# Mouse.net
KiCad netlist of a schematic drawn in EAGLE
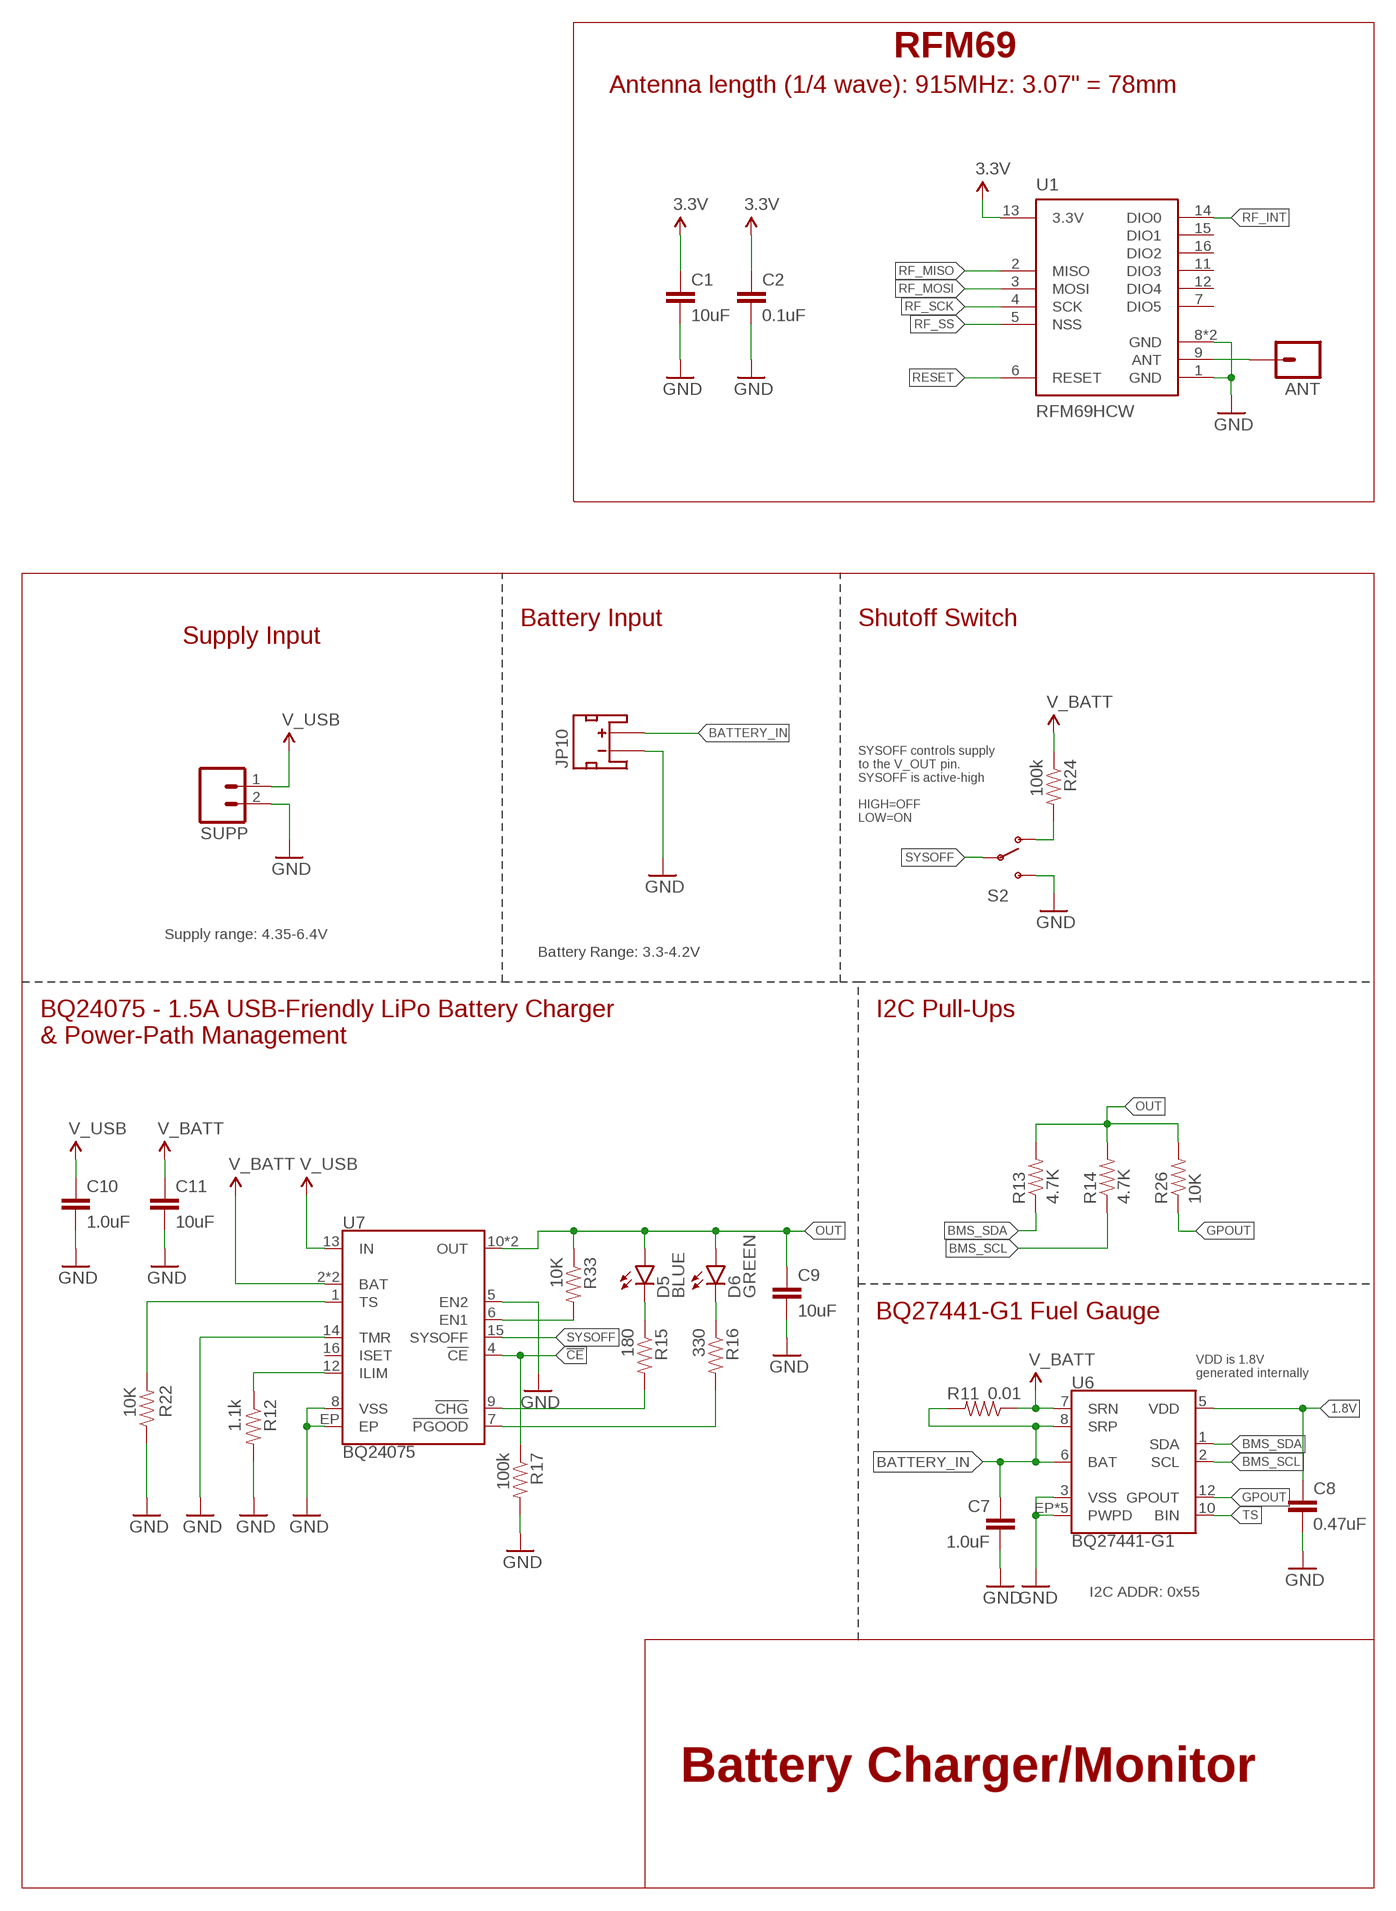
[diagram p0: schematic, sheet 1, part 1 of 2]
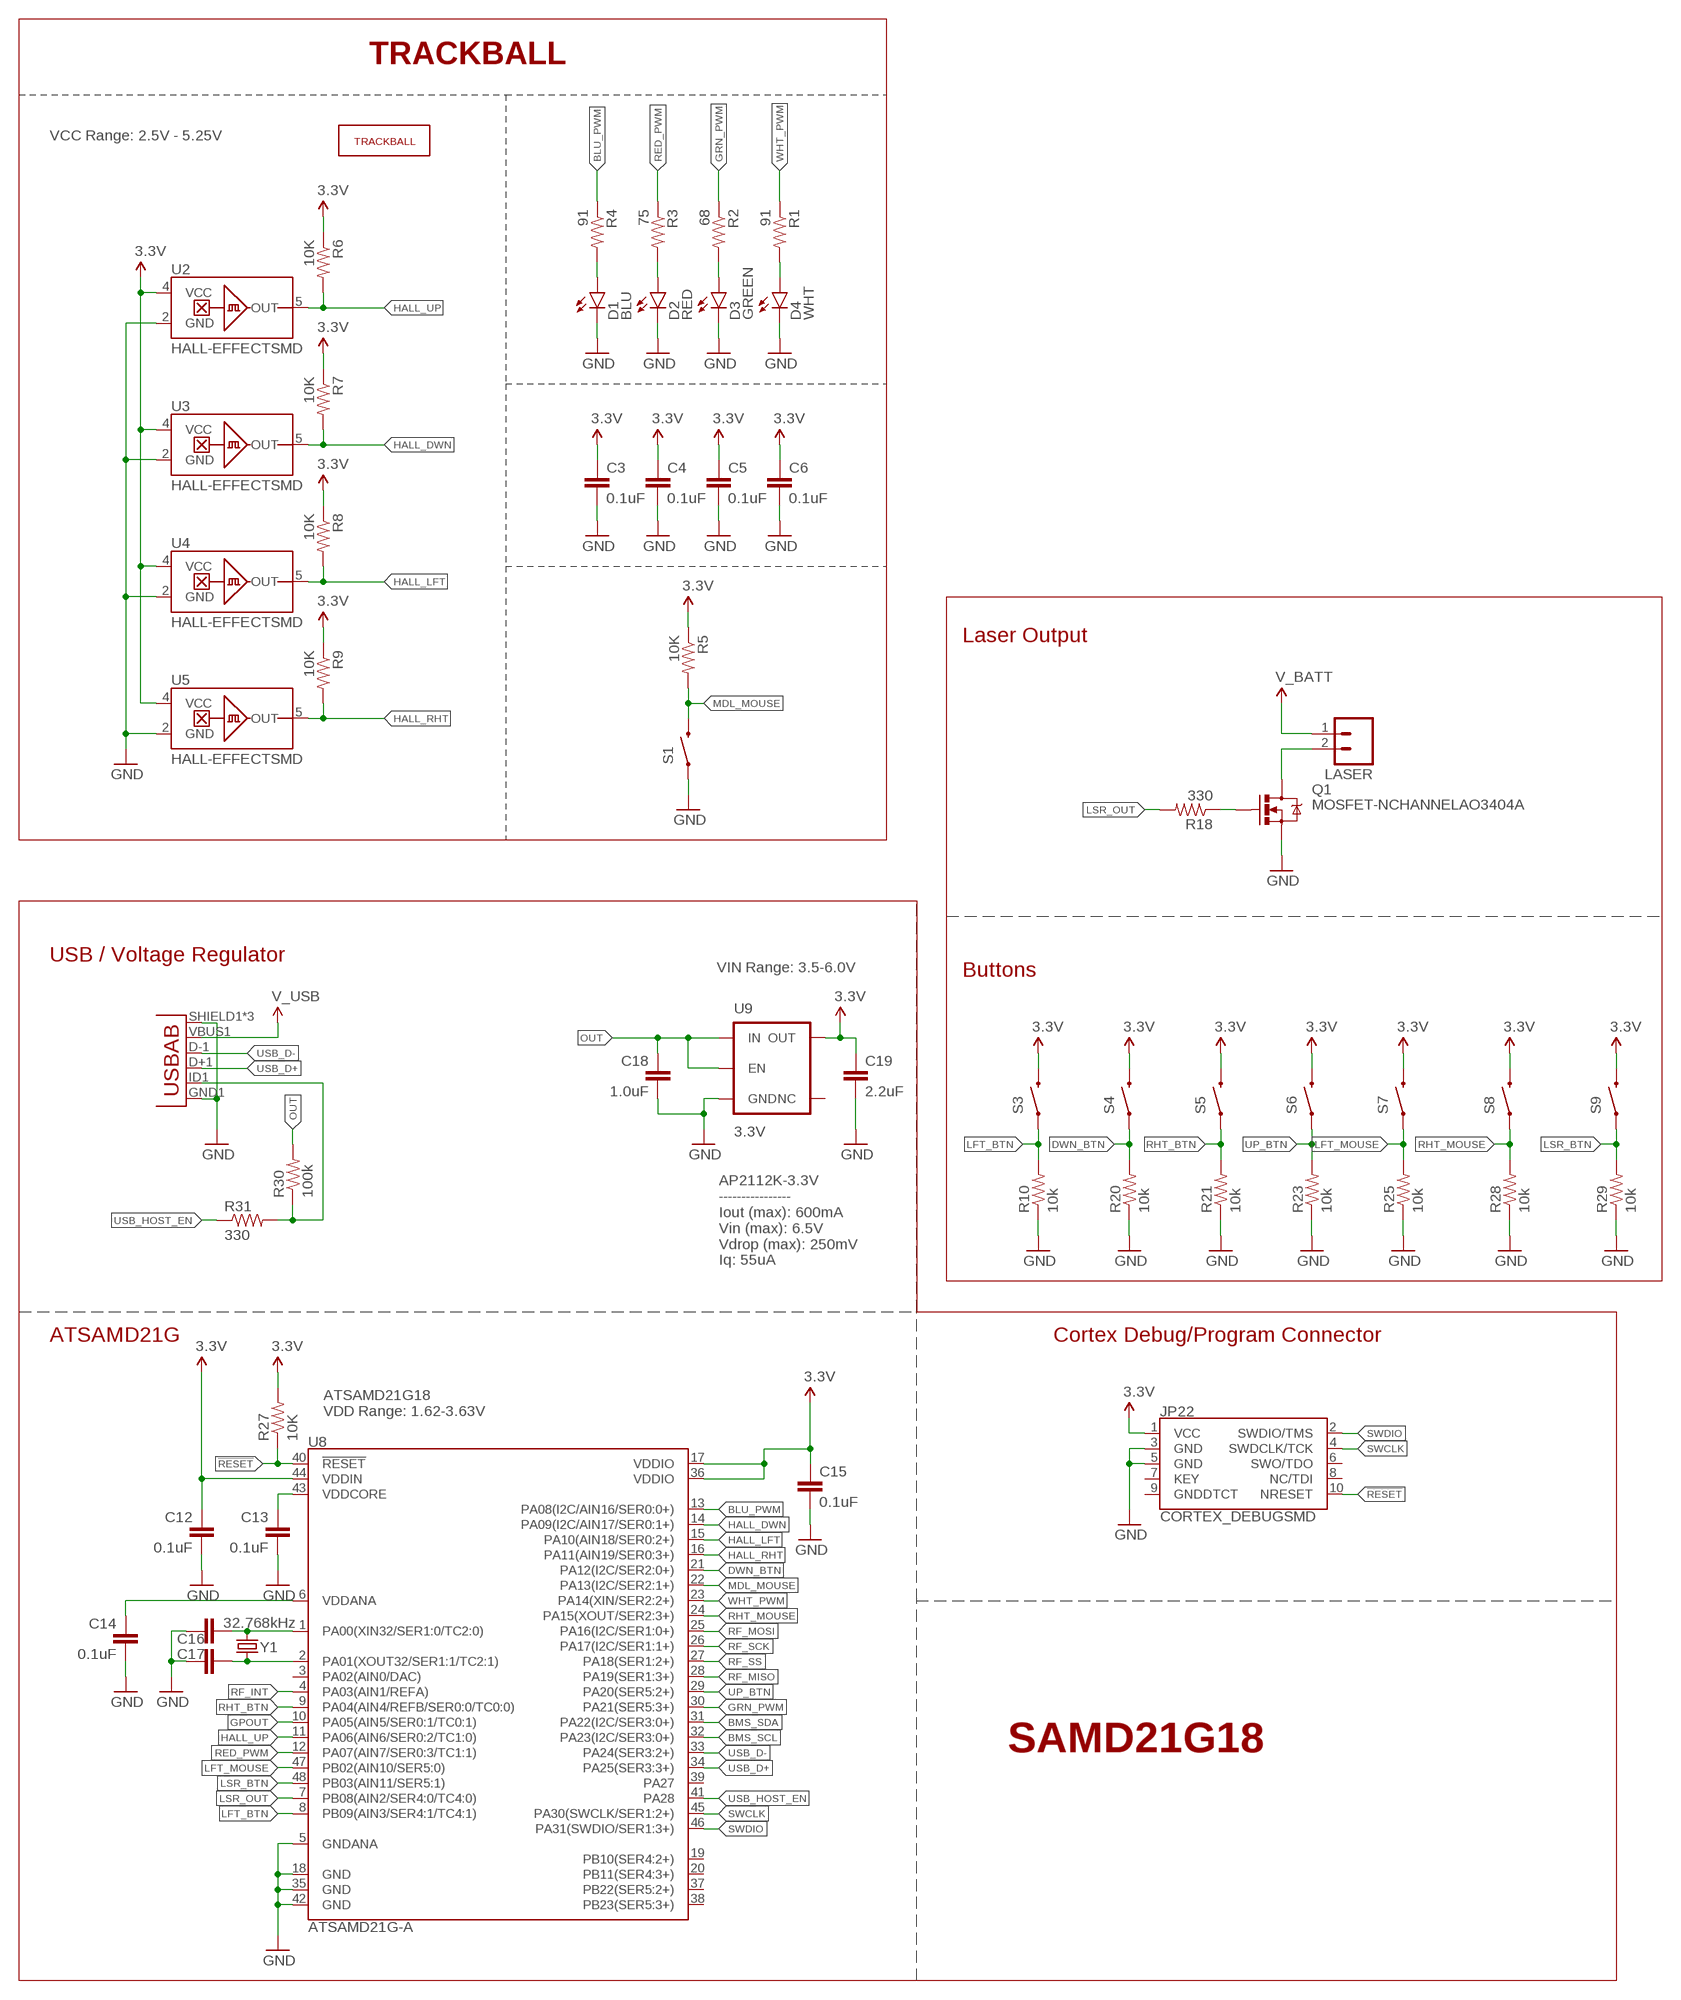
[diagram p1: schematic, sheet 1, part 2 of 2]

(export (version "E")
  (design (tool "Eeschema 10.0.6"))
  (components
    (comp (ref "ANT")
      (value "M01PTH_NO_SILK_YES_STOP")
      (footprint "eagle-import:1X01_NO_SILK")
      (libsource (lib "eagle-import") (part "M01PTH_NO_SILK_YES_STOP"))
    )
    (comp (ref "C1")
      (value "10uF")
      (footprint "eagle-import:1210")
      (libsource (lib "eagle-import") (part "10UF50V20%(1210)"))
    )
    (comp (ref "C2")
      (value "0.1uF")
      (footprint "eagle-import:0603-CAP")
      (libsource (lib "eagle-import") (part "0.1UF-25V(+80/-20%)(0603)"))
    )
    (comp (ref "C3")
      (value "0.1uF")
      (footprint "eagle-import:0603-CAP")
      (libsource (lib "eagle-import") (part "0.1UF-25V(+80/-20%)(0603)"))
    )
    (comp (ref "C4")
      (value "0.1uF")
      (footprint "eagle-import:0603-CAP")
      (libsource (lib "eagle-import") (part "0.1UF-25V(+80/-20%)(0603)"))
    )
    (comp (ref "C5")
      (value "0.1uF")
      (footprint "eagle-import:0603-CAP")
      (libsource (lib "eagle-import") (part "0.1UF-25V(+80/-20%)(0603)"))
    )
    (comp (ref "C6")
      (value "0.1uF")
      (footprint "eagle-import:0603-CAP")
      (libsource (lib "eagle-import") (part "0.1UF-25V(+80/-20%)(0603)"))
    )
    (comp (ref "C7")
      (value "1.0uF")
      (footprint "eagle-import:0603-CAP")
      (libsource (lib "eagle-import") (part "1.0UF-16V-10%(0603)"))
    )
    (comp (ref "C8")
      (value "0.47uF")
      (footprint "eagle-import:0603-CAP")
      (libsource (lib "eagle-import") (part "CAP0603-CAP"))
    )
    (comp (ref "C9")
      (value "10uF")
      (footprint "eagle-import:0805-CAP")
      (libsource (lib "eagle-import") (part "10UF10V10%(0805)"))
    )
    (comp (ref "C10")
      (value "1.0uF")
      (footprint "eagle-import:1206-CAP")
      (libsource (lib "eagle-import") (part "1.0UF50V10%(1206)"))
    )
    (comp (ref "C11")
      (value "10uF")
      (footprint "eagle-import:0805-CAP")
      (libsource (lib "eagle-import") (part "10UF10V10%(0805)"))
    )
    (comp (ref "C12")
      (value "0.1uF")
      (footprint "eagle-import:0603-CAP")
      (libsource (lib "eagle-import") (part "CAP0603-CAP"))
    )
    (comp (ref "C13")
      (value "0.1uF")
      (footprint "eagle-import:0603-CAP")
      (libsource (lib "eagle-import") (part "CAP0603-CAP"))
    )
    (comp (ref "C14")
      (value "0.1uF")
      (footprint "eagle-import:0603-CAP")
      (libsource (lib "eagle-import") (part "CAP0603-CAP"))
    )
    (comp (ref "C15")
      (value "0.1uF")
      (footprint "eagle-import:0603-CAP")
      (libsource (lib "eagle-import") (part "CAP0603-CAP"))
    )
    (comp (ref "C16")
      (value "15pF")
      (footprint "eagle-import:0603-CAP")
      (libsource (lib "eagle-import") (part "CAP0603-CAP"))
    )
    (comp (ref "C17")
      (value "15pF")
      (footprint "eagle-import:0603-CAP")
      (libsource (lib "eagle-import") (part "CAP0603-CAP"))
    )
    (comp (ref "C18")
      (value "1.0uF")
      (footprint "eagle-import:0805-CAP")
      (libsource (lib "eagle-import") (part "1.0UF-25V-+80/-20(0805){dblquote}"))
    )
    (comp (ref "C19")
      (value "2.2uF")
      (footprint "eagle-import:0603-CAP")
      (libsource (lib "eagle-import") (part "2.2UF-10V-20%(0603)"))
    )
    (comp (ref "D1")
      (value "BLU")
      (footprint "eagle-import:LED-0603")
      (libsource (lib "eagle-import") (part "LED-BLUE0603"))
    )
    (comp (ref "D2")
      (value "RED")
      (footprint "eagle-import:LED-0603")
      (libsource (lib "eagle-import") (part "LED-RED0603"))
    )
    (comp (ref "D3")
      (value "GREEN")
      (footprint "eagle-import:LED-0603")
      (libsource (lib "eagle-import") (part "LED-GREEN0603"))
    )
    (comp (ref "D4")
      (value "WHT")
      (footprint "eagle-import:LED-0603")
      (libsource (lib "eagle-import") (part "LED-WHITE0603"))
    )
    (comp (ref "D5")
      (value "BLUE")
      (footprint "eagle-import:LED-0603")
      (libsource (lib "eagle-import") (part "LED-BLUE0603"))
    )
    (comp (ref "D6")
      (value "GREEN")
      (footprint "eagle-import:LED-0603")
      (libsource (lib "eagle-import") (part "LED-RED0603"))
    )
    (comp (ref "JP10")
      (value "JST_2MM_MALE")
      (footprint "eagle-import:JST-2-SMD")
      (libsource (lib "eagle-import") (part "JST_2MM_MALE"))
    )
    (comp (ref "JP22")
      (value "CORTEX_DEBUGSMD")
      (footprint "eagle-import:SAMTECH_FTSH-105-01")
      (libsource (lib "eagle-import") (part "CORTEX_DEBUGSMD"))
    )
    (comp (ref "JP23")
      (value "USB-ABCONN-11794")
      (footprint "eagle-import:USB-AB-MICRO-SMD_V03")
      (libsource (lib "eagle-import") (part "USB-ABCONN-11794"))
    )
    (comp (ref "LASER")
      (value "M021X02_NO_SILK")
      (footprint "eagle-import:1X02_NO_SILK")
      (libsource (lib "eagle-import") (part "M021X02_NO_SILK"))
    )
    (comp (ref "Q1")
      (value "MOSFET-NCHANNELAO3404A")
      (footprint "eagle-import:SOT23-3")
      (libsource (lib "eagle-import") (part "MOSFET-NCHANNELAO3404A"))
    )
    (comp (ref "R1")
      (value "91")
      (footprint "eagle-import:0603-RES@2")
      (libsource (lib "eagle-import") (part "180OHM1/10W1%(0603)"))
    )
    (comp (ref "R2")
      (value "68")
      (footprint "eagle-import:0603-RES@2")
      (libsource (lib "eagle-import") (part "180OHM1/10W1%(0603)"))
    )
    (comp (ref "R3")
      (value "75")
      (footprint "eagle-import:0603-RES@2")
      (libsource (lib "eagle-import") (part "180OHM1/10W1%(0603)"))
    )
    (comp (ref "R4")
      (value "91")
      (footprint "eagle-import:0603-RES@2")
      (libsource (lib "eagle-import") (part "180OHM1/10W1%(0603)"))
    )
    (comp (ref "R5")
      (value "10K")
      (footprint "eagle-import:0603-RES@1")
      (libsource (lib "eagle-import") (part "10KOHM1/10W1%(0603)0603"))
    )
    (comp (ref "R6")
      (value "10K")
      (footprint "eagle-import:0603-RES@1")
      (libsource (lib "eagle-import") (part "10KOHM1/10W1%(0603)0603"))
    )
    (comp (ref "R7")
      (value "10K")
      (footprint "eagle-import:0603-RES@1")
      (libsource (lib "eagle-import") (part "10KOHM1/10W1%(0603)0603"))
    )
    (comp (ref "R8")
      (value "10K")
      (footprint "eagle-import:0603-RES@1")
      (libsource (lib "eagle-import") (part "10KOHM1/10W1%(0603)0603"))
    )
    (comp (ref "R9")
      (value "10K")
      (footprint "eagle-import:0603-RES@1")
      (libsource (lib "eagle-import") (part "10KOHM1/10W1%(0603)0603"))
    )
    (comp (ref "R10")
      (value "10k")
      (footprint "eagle-import:0603-RES")
      (libsource (lib "eagle-import") (part "330OHM1/10W1%(0603)"))
    )
    (comp (ref "R11")
      (value "0.01")
      (footprint "eagle-import:1206")
      (libsource (lib "eagle-import") (part "SparkFun-Resistors_RESISTOR1206"))
    )
    (comp (ref "R12")
      (value "1.1k")
      (footprint "eagle-import:0603-RES")
      (libsource (lib "eagle-import") (part "RESISTOR0603-RES"))
    )
    (comp (ref "R13")
      (value "4.7K")
      (footprint "eagle-import:0603-RES@2")
      (libsource (lib "eagle-import") (part "4.7KOHM-1/10W-1%(0603)"))
    )
    (comp (ref "R14")
      (value "4.7K")
      (footprint "eagle-import:0603-RES@2")
      (libsource (lib "eagle-import") (part "4.7KOHM-1/10W-1%(0603)"))
    )
    (comp (ref "R15")
      (value "180")
      (footprint "eagle-import:0603-RES@2")
      (libsource (lib "eagle-import") (part "180OHM1/10W1%(0603)"))
    )
    (comp (ref "R16")
      (value "330")
      (footprint "eagle-import:0603-RES@2")
      (libsource (lib "eagle-import") (part "1KOHM-1/10W-1%(0603)"))
    )
    (comp (ref "R17")
      (value "100k")
      (footprint "eagle-import:0603-RES")
      (libsource (lib "eagle-import") (part "100KOHM-1/10W-1%(0603)"))
    )
    (comp (ref "R18")
      (value "330")
      (footprint "eagle-import:0603-RES")
      (libsource (lib "eagle-import") (part "330OHM1/10W1%(0603)"))
    )
    (comp (ref "R20")
      (value "10k")
      (footprint "eagle-import:0603-RES")
      (libsource (lib "eagle-import") (part "330OHM1/10W1%(0603)"))
    )
    (comp (ref "R21")
      (value "10k")
      (footprint "eagle-import:0603-RES")
      (libsource (lib "eagle-import") (part "330OHM1/10W1%(0603)"))
    )
    (comp (ref "R22")
      (value "10K")
      (footprint "eagle-import:0603-RES")
      (libsource (lib "eagle-import") (part "10KOHM-1/10W-1%(0603)0603"))
    )
    (comp (ref "R23")
      (value "10k")
      (footprint "eagle-import:0603-RES")
      (libsource (lib "eagle-import") (part "330OHM1/10W1%(0603)"))
    )
    (comp (ref "R24")
      (value "100k")
      (footprint "eagle-import:0603-RES")
      (libsource (lib "eagle-import") (part "100KOHM-1/10W-1%(0603)"))
    )
    (comp (ref "R25")
      (value "10k")
      (footprint "eagle-import:0603-RES")
      (libsource (lib "eagle-import") (part "330OHM1/10W1%(0603)"))
    )
    (comp (ref "R26")
      (value "10K")
      (footprint "eagle-import:0603-RES")
      (libsource (lib "eagle-import") (part "10KOHM-1/10W-1%(0603)0603"))
    )
    (comp (ref "R27")
      (value "10K")
      (footprint "eagle-import:0603-RES")
      (libsource (lib "eagle-import") (part "10KOHM-1/10W-1%(0603)0603"))
    )
    (comp (ref "R28")
      (value "10k")
      (footprint "eagle-import:0603-RES")
      (libsource (lib "eagle-import") (part "330OHM1/10W1%(0603)"))
    )
    (comp (ref "R29")
      (value "10k")
      (footprint "eagle-import:0603-RES")
      (libsource (lib "eagle-import") (part "330OHM1/10W1%(0603)"))
    )
    (comp (ref "R30")
      (value "100k")
      (footprint "eagle-import:0603-RES")
      (libsource (lib "eagle-import") (part "100KOHM-1/10W-1%(0603)"))
    )
    (comp (ref "R31")
      (value "330")
      (footprint "eagle-import:0603-RES")
      (libsource (lib "eagle-import") (part "330OHM1/10W1%(0603)"))
    )
    (comp (ref "R33")
      (value "10K")
      (footprint "eagle-import:0603-RES")
      (libsource (lib "eagle-import") (part "10KOHM-1/10W-1%(0603)0603"))
    )
    (comp (ref "S1")
      (value "SWITCH-MOMENTARY-2SMD-2")
      (footprint "eagle-import:TACTILE_SWITCH_SMD-2")
      (libsource (lib "eagle-import") (part "SWITCH-MOMENTARY-2SMD-2"))
    )
    (comp (ref "S2")
      (value "SWITCH-SPDT-SMD-A")
      (footprint "eagle-import:SWITCH-SPST-SMD-A")
      (libsource (lib "eagle-import") (part "SWITCH-SPDT-SMD-A"))
    )
    (comp (ref "S3")
      (value "SWITCH-MOMENTARY-2SMD-4")
      (footprint "eagle-import:TACTILE_SWITCH_TALL")
      (libsource (lib "eagle-import") (part "SWITCH-MOMENTARY-2SMD-4"))
    )
    (comp (ref "S4")
      (value "SWITCH-MOMENTARY-2SMD-4")
      (footprint "eagle-import:TACTILE_SWITCH_TALL")
      (libsource (lib "eagle-import") (part "SWITCH-MOMENTARY-2SMD-4"))
    )
    (comp (ref "S5")
      (value "SWITCH-MOMENTARY-2SMD-4")
      (footprint "eagle-import:TACTILE_SWITCH_TALL")
      (libsource (lib "eagle-import") (part "SWITCH-MOMENTARY-2SMD-4"))
    )
    (comp (ref "S6")
      (value "SWITCH-MOMENTARY-2SMD-4")
      (footprint "eagle-import:TACTILE_SWITCH_TALL")
      (libsource (lib "eagle-import") (part "SWITCH-MOMENTARY-2SMD-4"))
    )
    (comp (ref "S7")
      (value "SWITCH-MOMENTARY-2SMD-4")
      (footprint "eagle-import:TACTILE_SWITCH_TALL")
      (libsource (lib "eagle-import") (part "SWITCH-MOMENTARY-2SMD-4"))
    )
    (comp (ref "S8")
      (value "SWITCH-MOMENTARY-2SMD-4")
      (footprint "eagle-import:TACTILE_SWITCH_TALL")
      (libsource (lib "eagle-import") (part "SWITCH-MOMENTARY-2SMD-4"))
    )
    (comp (ref "S9")
      (value "SWITCH-MOMENTARY-2SMD-4")
      (footprint "eagle-import:TACTILE_SWITCH_TALL")
      (libsource (lib "eagle-import") (part "SWITCH-MOMENTARY-2SMD-4"))
    )
    (comp (ref "SUPP")
      (value "M021X02_NO_SILK")
      (footprint "eagle-import:1X02_NO_SILK")
      (libsource (lib "eagle-import") (part "mike-temp_M021X02_NO_SILK"))
    )
    (comp (ref "U$1")
      (value "TRACKBALLMECH")
      (footprint "eagle-import:TRACKBALL")
      (libsource (lib "eagle-import") (part "TRACKBALLMECH"))
    )
    (comp (ref "U1")
      (value "RFM69HCW")
      (footprint "eagle-import:RFM69HCW-XXXS2")
      (libsource (lib "eagle-import") (part "RFM69HCW"))
    )
    (comp (ref "U2")
      (value "HALL-EFFECTSMD")
      (footprint "eagle-import:SC70")
      (libsource (lib "eagle-import") (part "HALL-EFFECTSMD"))
    )
    (comp (ref "U3")
      (value "HALL-EFFECTSMD")
      (footprint "eagle-import:SC70")
      (libsource (lib "eagle-import") (part "HALL-EFFECTSMD"))
    )
    (comp (ref "U4")
      (value "HALL-EFFECTSMD")
      (footprint "eagle-import:SC70")
      (libsource (lib "eagle-import") (part "HALL-EFFECTSMD"))
    )
    (comp (ref "U5")
      (value "HALL-EFFECTSMD")
      (footprint "eagle-import:SC70")
      (libsource (lib "eagle-import") (part "HALL-EFFECTSMD"))
    )
    (comp (ref "U6")
      (value "BQ27441-G1")
      (footprint "eagle-import:PDSO-N12")
      (libsource (lib "eagle-import") (part "BQ27441-G1"))
    )
    (comp (ref "U7")
      (value "BQ24075")
      (footprint "eagle-import:PVQFN-N16")
      (libsource (lib "eagle-import") (part "BQ24075"))
    )
    (comp (ref "U8")
      (value "ATSAMD21G-A")
      (footprint "eagle-import:TQFP-48")
      (libsource (lib "eagle-import") (part "ATSAMD21G-A"))
    )
    (comp (ref "U9")
      (value "3.3V")
      (footprint "eagle-import:SOT23-5")
      (libsource (lib "eagle-import") (part "V_REG_AP2112K-3.3V"))
    )
    (comp (ref "Y1")
      (value "32.768kHz")
      (footprint "eagle-import:CRYSTAL-SMD-3.2X1.5MM")
      (libsource (lib "eagle-import") (part "CRYSTAL3.2X1.5MM"))
    )
  )
  (nets
    (net (code "1") (name "/~{CE}") (class "Default")
      (node (ref "R17") (pin "1") (pinfunction "1_1") (pintype "passive"))
      (node (ref "U7") (pin "4") (pinfunction "~{CE}_4") (pintype "bidirectional"))
    )
    (net (code "2") (name "/~{RESET}") (class "Default")
      (node (ref "JP22") (pin "10") (pinfunction "NRESET_10") (pintype "bidirectional"))
      (node (ref "R27") (pin "1") (pinfunction "1_1") (pintype "passive"))
      (node (ref "U8") (pin "40") (pinfunction "~{RESET}_40") (pintype "bidirectional"))
    )
    (net (code "3") (name "1.8V") (class "Default")
      (node (ref "C8") (pin "1") (pinfunction "1_1") (pintype "passive"))
      (node (ref "U6") (pin "5") (pinfunction "VDD_5") (pintype "bidirectional"))
    )
    (net (code "4") (name "3.3V") (class "Default")
      (node (ref "C1") (pin "1") (pinfunction "1_1") (pintype "passive"))
      (node (ref "C12") (pin "1") (pinfunction "1_1") (pintype "passive"))
      (node (ref "C15") (pin "1") (pinfunction "1_1") (pintype "passive"))
      (node (ref "C19") (pin "1") (pinfunction "1_1") (pintype "passive"))
      (node (ref "C2") (pin "1") (pinfunction "1_1") (pintype "passive"))
      (node (ref "C3") (pin "1") (pinfunction "1_1") (pintype "passive"))
      (node (ref "C4") (pin "1") (pinfunction "1_1") (pintype "passive"))
      (node (ref "C5") (pin "1") (pinfunction "1_1") (pintype "passive"))
      (node (ref "C6") (pin "1") (pinfunction "1_1") (pintype "passive"))
      (node (ref "JP22") (pin "1") (pinfunction "VCC_1") (pintype "bidirectional"))
      (node (ref "R27") (pin "2") (pinfunction "2_2") (pintype "passive"))
      (node (ref "R5") (pin "1") (pinfunction "1_1") (pintype "passive"))
      (node (ref "R6") (pin "1") (pinfunction "1_1") (pintype "passive"))
      (node (ref "R7") (pin "1") (pinfunction "1_1") (pintype "passive"))
      (node (ref "R8") (pin "1") (pinfunction "1_1") (pintype "passive"))
      (node (ref "R9") (pin "1") (pinfunction "1_1") (pintype "passive"))
      (node (ref "S3") (pin "B2") (pinfunction "2_B2") (pintype "passive"))
      (node (ref "S4") (pin "B2") (pinfunction "2_B2") (pintype "passive"))
      (node (ref "S5") (pin "B2") (pinfunction "2_B2") (pintype "passive"))
      (node (ref "S6") (pin "B2") (pinfunction "2_B2") (pintype "passive"))
      (node (ref "S7") (pin "B2") (pinfunction "2_B2") (pintype "passive"))
      (node (ref "S8") (pin "B2") (pinfunction "2_B2") (pintype "passive"))
      (node (ref "S9") (pin "B2") (pinfunction "2_B2") (pintype "passive"))
      (node (ref "U1") (pin "13") (pinfunction "3.3V_13") (pintype "power_in"))
      (node (ref "U2") (pin "4") (pinfunction "VCC_4") (pintype "bidirectional"))
      (node (ref "U3") (pin "4") (pinfunction "VCC_4") (pintype "bidirectional"))
      (node (ref "U4") (pin "4") (pinfunction "VCC_4") (pintype "bidirectional"))
      (node (ref "U5") (pin "4") (pinfunction "VCC_4") (pintype "bidirectional"))
      (node (ref "U8") (pin "17") (pinfunction "VDDIO_17") (pintype "bidirectional"))
      (node (ref "U8") (pin "36") (pinfunction "VDDIO_36") (pintype "bidirectional"))
      (node (ref "U8") (pin "44") (pinfunction "VDDIN_44") (pintype "bidirectional"))
      (node (ref "U9") (pin "5") (pinfunction "OUT_5") (pintype "passive"))
    )
    (net (code "5") (name "BATTERY_IN") (class "Default")
      (node (ref "C7") (pin "1") (pinfunction "1_1") (pintype "passive"))
      (node (ref "JP10") (pin "2") (pinfunction "+_2") (pintype "bidirectional"))
      (node (ref "R11") (pin "2") (pinfunction "2_2") (pintype "passive"))
      (node (ref "U6") (pin "6") (pinfunction "BAT_6") (pintype "bidirectional"))
      (node (ref "U6") (pin "8") (pinfunction "SRP_8") (pintype "bidirectional"))
    )
    (net (code "6") (name "BLU_PWM") (class "Default")
      (node (ref "R4") (pin "1") (pinfunction "1_1") (pintype "passive"))
      (node (ref "U8") (pin "13") (pinfunction "PA08(I2C/AIN16/SER0:0+)_13") (pintype "bidirectional"))
    )
    (net (code "7") (name "BMS_SCL") (class "Default")
      (node (ref "R14") (pin "1") (pinfunction "1_1") (pintype "passive"))
      (node (ref "U6") (pin "2") (pinfunction "SCL_2") (pintype "bidirectional"))
      (node (ref "U8") (pin "32") (pinfunction "PA23(I2C/SER3:0+)_32") (pintype "bidirectional"))
    )
    (net (code "8") (name "BMS_SDA") (class "Default")
      (node (ref "R13") (pin "1") (pinfunction "1_1") (pintype "passive"))
      (node (ref "U6") (pin "1") (pinfunction "SDA_1") (pintype "bidirectional"))
      (node (ref "U8") (pin "31") (pinfunction "PA22(I2C/SER3:0+)_31") (pintype "bidirectional"))
    )
    (net (code "9") (name "DWN_BTN") (class "Default")
      (node (ref "R20") (pin "2") (pinfunction "2_2") (pintype "passive"))
      (node (ref "S4") (pin "A2") (pinfunction "1_A2") (pintype "passive"))
      (node (ref "U8") (pin "21") (pinfunction "PA12(I2C/SER2:0+)_21") (pintype "bidirectional"))
    )
    (net (code "10") (name "GND") (class "Default")
      (node (ref "C1") (pin "2") (pinfunction "2_2") (pintype "passive"))
      (node (ref "C10") (pin "2") (pinfunction "2_2") (pintype "passive"))
      (node (ref "C11") (pin "2") (pinfunction "2_2") (pintype "passive"))
      (node (ref "C12") (pin "2") (pinfunction "2_2") (pintype "passive"))
      (node (ref "C13") (pin "2") (pinfunction "2_2") (pintype "passive"))
      (node (ref "C14") (pin "2") (pinfunction "2_2") (pintype "passive"))
      (node (ref "C15") (pin "2") (pinfunction "2_2") (pintype "passive"))
      (node (ref "C16") (pin "1") (pinfunction "1_1") (pintype "passive"))
      (node (ref "C17") (pin "2") (pinfunction "2_2") (pintype "passive"))
      (node (ref "C18") (pin "2") (pinfunction "2_2") (pintype "passive"))
      (node (ref "C19") (pin "2") (pinfunction "2_2") (pintype "passive"))
      (node (ref "C2") (pin "2") (pinfunction "2_2") (pintype "passive"))
      (node (ref "C3") (pin "2") (pinfunction "2_2") (pintype "passive"))
      (node (ref "C4") (pin "2") (pinfunction "2_2") (pintype "passive"))
      (node (ref "C5") (pin "2") (pinfunction "2_2") (pintype "passive"))
      (node (ref "C6") (pin "2") (pinfunction "2_2") (pintype "passive"))
      (node (ref "C7") (pin "2") (pinfunction "2_2") (pintype "passive"))
      (node (ref "C8") (pin "2") (pinfunction "2_2") (pintype "passive"))
      (node (ref "C9") (pin "2") (pinfunction "2_2") (pintype "passive"))
      (node (ref "D1") (pin "C") (pinfunction "C_C") (pintype "passive"))
      (node (ref "D2") (pin "C") (pinfunction "C_C") (pintype "passive"))
      (node (ref "D3") (pin "C") (pinfunction "C_C") (pintype "passive"))
      (node (ref "D4") (pin "C") (pinfunction "C_C") (pintype "passive"))
      (node (ref "JP10") (pin "1") (pinfunction "-_1") (pintype "bidirectional"))
      (node (ref "JP22") (pin "3") (pinfunction "GND_3") (pintype "bidirectional"))
      (node (ref "JP22") (pin "5") (pinfunction "GND_5") (pintype "bidirectional"))
      (node (ref "JP23") (pin "GND1") (pinfunction "GND_GND1") (pintype "bidirectional"))
      (node (ref "JP23") (pin "SHIELD1") (pinfunction "SHIELD_SHIELD1") (pintype "bidirectional"))
      (node (ref "JP23") (pin "SHIELD2") (pinfunction "SHIELD_SHIELD2") (pintype "bidirectional"))
      (node (ref "JP23") (pin "SHIELD3") (pinfunction "SHIELD_SHIELD3") (pintype "bidirectional"))
      (node (ref "Q1") (pin "2") (pinfunction "S_2") (pintype "passive"))
      (node (ref "R10") (pin "1") (pinfunction "1_1") (pintype "passive"))
      (node (ref "R12") (pin "2") (pinfunction "2_2") (pintype "passive"))
      (node (ref "R17") (pin "2") (pinfunction "2_2") (pintype "passive"))
      (node (ref "R20") (pin "1") (pinfunction "1_1") (pintype "passive"))
      (node (ref "R21") (pin "1") (pinfunction "1_1") (pintype "passive"))
      (node (ref "R22") (pin "1") (pinfunction "1_1") (pintype "passive"))
      (node (ref "R23") (pin "1") (pinfunction "1_1") (pintype "passive"))
      (node (ref "R25") (pin "1") (pinfunction "1_1") (pintype "passive"))
      (node (ref "R28") (pin "1") (pinfunction "1_1") (pintype "passive"))
      (node (ref "R29") (pin "1") (pinfunction "1_1") (pintype "passive"))
      (node (ref "S1") (pin "2") (pinfunction "1_2") (pintype "passive"))
      (node (ref "S2") (pin "3") (pinfunction "S_3") (pintype "passive"))
      (node (ref "SUPP") (pin "2") (pinfunction "2_2") (pintype "passive"))
      (node (ref "U1") (pin "1") (pinfunction "GND_1") (pintype "power_in"))
      (node (ref "U1") (pin "10") (pinfunction "GND_10") (pintype "power_in"))
      (node (ref "U1") (pin "8") (pinfunction "GND_8") (pintype "power_in"))
      (node (ref "U2") (pin "2") (pinfunction "GND_2") (pintype "bidirectional"))
      (node (ref "U3") (pin "2") (pinfunction "GND_2") (pintype "bidirectional"))
      (node (ref "U4") (pin "2") (pinfunction "GND_2") (pintype "bidirectional"))
      (node (ref "U5") (pin "2") (pinfunction "GND_2") (pintype "bidirectional"))
      (node (ref "U6") (pin "3") (pinfunction "VSS_3") (pintype "bidirectional"))
      (node (ref "U6") (pin "EP") (pinfunction "PWPD_EP") (pintype "bidirectional"))
      (node (ref "U6") (pin "EP1") (pinfunction "PWPD_EP1") (pintype "bidirectional"))
      (node (ref "U6") (pin "EP2") (pinfunction "PWPD_EP2") (pintype "bidirectional"))
      (node (ref "U6") (pin "EP3") (pinfunction "PWPD_EP3") (pintype "bidirectional"))
      (node (ref "U6") (pin "EP4") (pinfunction "PWPD_EP4") (pintype "bidirectional"))
      (node (ref "U7") (pin "14") (pinfunction "TMR_14") (pintype "bidirectional"))
      (node (ref "U7") (pin "5") (pinfunction "EN2_5") (pintype "bidirectional"))
      (node (ref "U7") (pin "8") (pinfunction "VSS_8") (pintype "bidirectional"))
      (node (ref "U7") (pin "EP") (pinfunction "EP_EP") (pintype "bidirectional"))
      (node (ref "U8") (pin "18") (pinfunction "GND_18") (pintype "bidirectional"))
      (node (ref "U8") (pin "35") (pinfunction "GND_35") (pintype "bidirectional"))
      (node (ref "U8") (pin "42") (pinfunction "GND_42") (pintype "bidirectional"))
      (node (ref "U8") (pin "5") (pinfunction "GNDANA_5") (pintype "bidirectional"))
      (node (ref "U9") (pin "2") (pinfunction "GND_2") (pintype "input"))
    )
    (net (code "11") (name "GPOUT") (class "Default")
      (node (ref "R26") (pin "1") (pinfunction "1_1") (pintype "passive"))
      (node (ref "U6") (pin "12") (pinfunction "GPOUT_12") (pintype "bidirectional"))
      (node (ref "U8") (pin "10") (pinfunction "PA05(AIN5/SER0:1/TC0:1)_10") (pintype "bidirectional"))
    )
    (net (code "12") (name "GRN_PWM") (class "Default")
      (node (ref "R2") (pin "1") (pinfunction "1_1") (pintype "passive"))
      (node (ref "U8") (pin "30") (pinfunction "PA21(SER5:3+)_30") (pintype "bidirectional"))
    )
    (net (code "13") (name "HALL_DWN") (class "Default")
      (node (ref "R7") (pin "2") (pinfunction "2_2") (pintype "passive"))
      (node (ref "U3") (pin "5") (pinfunction "OUT_5") (pintype "bidirectional"))
      (node (ref "U8") (pin "14") (pinfunction "PA09(I2C/AIN17/SER0:1+)_14") (pintype "bidirectional"))
    )
    (net (code "14") (name "HALL_LFT") (class "Default")
      (node (ref "R8") (pin "2") (pinfunction "2_2") (pintype "passive"))
      (node (ref "U4") (pin "5") (pinfunction "OUT_5") (pintype "bidirectional"))
      (node (ref "U8") (pin "15") (pinfunction "PA10(AIN18/SER0:2+)_15") (pintype "bidirectional"))
    )
    (net (code "15") (name "HALL_RHT") (class "Default")
      (node (ref "R9") (pin "2") (pinfunction "2_2") (pintype "passive"))
      (node (ref "U5") (pin "5") (pinfunction "OUT_5") (pintype "bidirectional"))
      (node (ref "U8") (pin "16") (pinfunction "PA11(AIN19/SER0:3+)_16") (pintype "bidirectional"))
    )
    (net (code "16") (name "HALL_UP") (class "Default")
      (node (ref "R6") (pin "2") (pinfunction "2_2") (pintype "passive"))
      (node (ref "U2") (pin "5") (pinfunction "OUT_5") (pintype "bidirectional"))
      (node (ref "U8") (pin "11") (pinfunction "PA06(AIN6/SER0:2/TC1:0)_11") (pintype "bidirectional"))
    )
    (net (code "17") (name "LFT_BTN") (class "Default")
      (node (ref "R10") (pin "2") (pinfunction "2_2") (pintype "passive"))
      (node (ref "S3") (pin "A2") (pinfunction "1_A2") (pintype "passive"))
      (node (ref "U8") (pin "8") (pinfunction "PB09(AIN3/SER4:1/TC4:1)_8") (pintype "bidirectional"))
    )
    (net (code "18") (name "LFT_MOUSE") (class "Default")
      (node (ref "R25") (pin "2") (pinfunction "2_2") (pintype "passive"))
      (node (ref "S7") (pin "A2") (pinfunction "1_A2") (pintype "passive"))
      (node (ref "U8") (pin "47") (pinfunction "PB02(AIN10/SER5:0)_47") (pintype "bidirectional"))
    )
    (net (code "19") (name "LSR_BTN") (class "Default")
      (node (ref "R29") (pin "2") (pinfunction "2_2") (pintype "passive"))
      (node (ref "S9") (pin "A2") (pinfunction "1_A2") (pintype "passive"))
      (node (ref "U8") (pin "48") (pinfunction "PB03(AIN11/SER5:1)_48") (pintype "bidirectional"))
    )
    (net (code "20") (name "LSR_OUT") (class "Default")
      (node (ref "R18") (pin "2") (pinfunction "2_2") (pintype "passive"))
      (node (ref "U8") (pin "7") (pinfunction "PB08(AIN2/SER4:0/TC4:0)_7") (pintype "bidirectional"))
    )
    (net (code "21") (name "MDL_MOUSE") (class "Default")
      (node (ref "R5") (pin "2") (pinfunction "2_2") (pintype "passive"))
      (node (ref "S1") (pin "1") (pinfunction "2_1") (pintype "passive"))
      (node (ref "U8") (pin "22") (pinfunction "PA13(I2C/SER2:1+)_22") (pintype "bidirectional"))
    )
    (net (code "22") (name "Net-(D1-PadA)") (class "Default")
      (node (ref "D1") (pin "A") (pinfunction "A_A") (pintype "passive"))
      (node (ref "R4") (pin "2") (pinfunction "2_2") (pintype "passive"))
    )
    (net (code "23") (name "Net-(D2-PadA)") (class "Default")
      (node (ref "D2") (pin "A") (pinfunction "A_A") (pintype "passive"))
      (node (ref "R3") (pin "2") (pinfunction "2_2") (pintype "passive"))
    )
    (net (code "24") (name "Net-(D3-PadA)") (class "Default")
      (node (ref "D3") (pin "A") (pinfunction "A_A") (pintype "passive"))
      (node (ref "R2") (pin "2") (pinfunction "2_2") (pintype "passive"))
    )
    (net (code "25") (name "Net-(D4-PadA)") (class "Default")
      (node (ref "D4") (pin "A") (pinfunction "A_A") (pintype "passive"))
      (node (ref "R1") (pin "2") (pinfunction "2_2") (pintype "passive"))
    )
    (net (code "26") (name "Net-(D5-PadC)") (class "Default")
      (node (ref "D5") (pin "C") (pinfunction "C_C") (pintype "passive"))
      (node (ref "R15") (pin "1") (pinfunction "1_1") (pintype "passive"))
    )
    (net (code "27") (name "Net-(D6-PadC)") (class "Default")
      (node (ref "D6") (pin "C") (pinfunction "C_C") (pintype "passive"))
      (node (ref "R16") (pin "1") (pinfunction "1_1") (pintype "passive"))
    )
    (net (code "28") (name "Net-(JP23-USBID)") (class "Default")
      (node (ref "JP23") (pin "ID1") (pinfunction "USBID_ID1") (pintype "bidirectional"))
      (node (ref "R30") (pin "1") (pinfunction "1_1") (pintype "passive"))
      (node (ref "R31") (pin "2") (pinfunction "2_2") (pintype "passive"))
    )
    (net (code "29") (name "Net-(Q1-D)") (class "Default")
      (node (ref "LASER") (pin "2") (pinfunction "2_2") (pintype "passive"))
      (node (ref "Q1") (pin "3") (pinfunction "D_3") (pintype "passive"))
    )
    (net (code "30") (name "Net-(Q1-G)") (class "Default")
      (node (ref "Q1") (pin "1") (pinfunction "G_1") (pintype "passive"))
      (node (ref "R18") (pin "1") (pinfunction "1_1") (pintype "passive"))
    )
    (net (code "31") (name "Net-(S2-O)") (class "Default")
      (node (ref "R24") (pin "2") (pinfunction "2_2") (pintype "passive"))
      (node (ref "S2") (pin "1") (pinfunction "O_1") (pintype "passive"))
    )
    (net (code "32") (name "Net-(U1-ANT)") (class "Default")
      (node (ref "ANT") (pin "1") (pinfunction "1_1") (pintype "passive"))
      (node (ref "U1") (pin "9") (pinfunction "ANT_9") (pintype "passive"))
    )
    (net (code "33") (name "Net-(U7-EN1)") (class "Default")
      (node (ref "R33") (pin "2") (pinfunction "2_2") (pintype "passive"))
      (node (ref "U7") (pin "6") (pinfunction "EN1_6") (pintype "bidirectional"))
    )
    (net (code "34") (name "Net-(U7-ILIM)") (class "Default")
      (node (ref "R12") (pin "1") (pinfunction "1_1") (pintype "passive"))
      (node (ref "U7") (pin "12") (pinfunction "ILIM_12") (pintype "bidirectional"))
    )
    (net (code "35") (name "Net-(U7-~{CHG})") (class "Default")
      (node (ref "R15") (pin "2") (pinfunction "2_2") (pintype "passive"))
      (node (ref "U7") (pin "9") (pinfunction "~{CHG}_9") (pintype "bidirectional"))
    )
    (net (code "36") (name "Net-(U7-~{PGOOD})") (class "Default")
      (node (ref "R16") (pin "2") (pinfunction "2_2") (pintype "passive"))
      (node (ref "U7") (pin "7") (pinfunction "~{PGOOD}_7") (pintype "bidirectional"))
    )
    (net (code "37") (name "Net-(U8-PA00(XIN32{slash}SER1:0{slash}TC2:0))") (class "Default")
      (node (ref "C16") (pin "2") (pinfunction "2_2") (pintype "passive"))
      (node (ref "U8") (pin "1") (pinfunction "PA00(XIN32/SER1:0/TC2:0)_1") (pintype "bidirectional"))
      (node (ref "Y1") (pin "P$2") (pinfunction "2_P$2") (pintype "passive"))
    )
    (net (code "38") (name "Net-(U8-PA01(XOUT32{slash}SER1:1{slash}TC2:1))") (class "Default")
      (node (ref "C17") (pin "1") (pinfunction "1_1") (pintype "passive"))
      (node (ref "U8") (pin "2") (pinfunction "PA01(XOUT32/SER1:1/TC2:1)_2") (pintype "bidirectional"))
      (node (ref "Y1") (pin "P$1") (pinfunction "1_P$1") (pintype "passive"))
    )
    (net (code "39") (name "Net-(U8-VDDANA)") (class "Default")
      (node (ref "C14") (pin "1") (pinfunction "1_1") (pintype "passive"))
      (node (ref "U8") (pin "6") (pinfunction "VDDANA_6") (pintype "bidirectional"))
    )
    (net (code "40") (name "Net-(U8-VDDCORE)") (class "Default")
      (node (ref "C13") (pin "1") (pinfunction "1_1") (pintype "passive"))
      (node (ref "U8") (pin "43") (pinfunction "VDDCORE_43") (pintype "bidirectional"))
    )
    (net (code "41") (name "OUT") (class "Default")
      (node (ref "C18") (pin "1") (pinfunction "1_1") (pintype "passive"))
      (node (ref "C9") (pin "1") (pinfunction "1_1") (pintype "passive"))
      (node (ref "D5") (pin "A") (pinfunction "A_A") (pintype "passive"))
      (node (ref "D6") (pin "A") (pinfunction "A_A") (pintype "passive"))
      (node (ref "R13") (pin "2") (pinfunction "2_2") (pintype "passive"))
      (node (ref "R14") (pin "2") (pinfunction "2_2") (pintype "passive"))
      (node (ref "R26") (pin "2") (pinfunction "2_2") (pintype "passive"))
      (node (ref "R30") (pin "2") (pinfunction "2_2") (pintype "passive"))
      (node (ref "R33") (pin "1") (pinfunction "1_1") (pintype "passive"))
      (node (ref "U7") (pin "10") (pinfunction "OUT_10") (pintype "bidirectional"))
      (node (ref "U7") (pin "11") (pinfunction "OUT_11") (pintype "bidirectional"))
      (node (ref "U9") (pin "1") (pinfunction "IN_1") (pintype "input"))
      (node (ref "U9") (pin "3") (pinfunction "EN_3") (pintype "input"))
    )
    (net (code "42") (name "RED_PWM") (class "Default")
      (node (ref "R3") (pin "1") (pinfunction "1_1") (pintype "passive"))
      (node (ref "U8") (pin "12") (pinfunction "PA07(AIN7/SER0:3/TC1:1)_12") (pintype "bidirectional"))
    )
    (net (code "43") (name "RESET") (class "Default")
      (node (ref "U1") (pin "6") (pinfunction "RESET_6") (pintype "input"))
    )
    (net (code "44") (name "RF_INT") (class "Default")
      (node (ref "U1") (pin "14") (pinfunction "DIO0_14") (pintype "bidirectional"))
      (node (ref "U8") (pin "4") (pinfunction "PA03(AIN1/REFA)_4") (pintype "bidirectional"))
    )
    (net (code "45") (name "RF_MISO") (class "Default")
      (node (ref "U1") (pin "2") (pinfunction "MISO_2") (pintype "bidirectional"))
      (node (ref "U8") (pin "28") (pinfunction "PA19(SER1:3+)_28") (pintype "bidirectional"))
    )
    (net (code "46") (name "RF_MOSI") (class "Default")
      (node (ref "U1") (pin "3") (pinfunction "MOSI_3") (pintype "input"))
      (node (ref "U8") (pin "25") (pinfunction "PA16(I2C/SER1:0+)_25") (pintype "bidirectional"))
    )
    (net (code "47") (name "RF_SCK") (class "Default")
      (node (ref "U1") (pin "4") (pinfunction "SCK_4") (pintype "input"))
      (node (ref "U8") (pin "26") (pinfunction "PA17(I2C/SER1:1+)_26") (pintype "bidirectional"))
    )
    (net (code "48") (name "RF_SS") (class "Default")
      (node (ref "U1") (pin "5") (pinfunction "NSS_5") (pintype "input"))
      (node (ref "U8") (pin "27") (pinfunction "PA18(SER1:2+)_27") (pintype "bidirectional"))
    )
    (net (code "49") (name "RHT_BTN") (class "Default")
      (node (ref "R21") (pin "2") (pinfunction "2_2") (pintype "passive"))
      (node (ref "S5") (pin "A2") (pinfunction "1_A2") (pintype "passive"))
      (node (ref "U8") (pin "9") (pinfunction "PA04(AIN4/REFB/SER0:0/TC0:0)_9") (pintype "bidirectional"))
    )
    (net (code "50") (name "RHT_MOUSE") (class "Default")
      (node (ref "R28") (pin "2") (pinfunction "2_2") (pintype "passive"))
      (node (ref "S8") (pin "A2") (pinfunction "1_A2") (pintype "passive"))
      (node (ref "U8") (pin "24") (pinfunction "PA15(XOUT/SER2:3+)_24") (pintype "bidirectional"))
    )
    (net (code "51") (name "SWCLK") (class "Default")
      (node (ref "JP22") (pin "4") (pinfunction "SWDCLK/TCK_4") (pintype "bidirectional"))
      (node (ref "U8") (pin "45") (pinfunction "PA30(SWCLK/SER1:2+)_45") (pintype "bidirectional"))
    )
    (net (code "52") (name "SWDIO") (class "Default")
      (node (ref "JP22") (pin "2") (pinfunction "SWDIO/TMS_2") (pintype "bidirectional"))
      (node (ref "U8") (pin "46") (pinfunction "PA31(SWDIO/SER1:3+)_46") (pintype "bidirectional"))
    )
    (net (code "53") (name "SYSOFF") (class "Default")
      (node (ref "S2") (pin "2") (pinfunction "P_2") (pintype "passive"))
      (node (ref "U7") (pin "15") (pinfunction "SYSOFF_15") (pintype "bidirectional"))
    )
    (net (code "54") (name "TS") (class "Default")
      (node (ref "R22") (pin "2") (pinfunction "2_2") (pintype "passive"))
      (node (ref "U6") (pin "10") (pinfunction "BIN_10") (pintype "bidirectional"))
      (node (ref "U7") (pin "1") (pinfunction "TS_1") (pintype "bidirectional"))
    )
    (net (code "55") (name "UP_BTN") (class "Default")
      (node (ref "R23") (pin "2") (pinfunction "2_2") (pintype "passive"))
      (node (ref "S6") (pin "A2") (pinfunction "1_A2") (pintype "passive"))
      (node (ref "U8") (pin "29") (pinfunction "PA20(SER5:2+)_29") (pintype "bidirectional"))
    )
    (net (code "56") (name "USB_D+") (class "Default")
      (node (ref "JP23") (pin "D+1") (pinfunction "D+_D+1") (pintype "bidirectional"))
      (node (ref "U8") (pin "34") (pinfunction "PA25(SER3:3+)_34") (pintype "bidirectional"))
    )
    (net (code "57") (name "USB_D-") (class "Default")
      (node (ref "JP23") (pin "D-1") (pinfunction "D-_D-1") (pintype "bidirectional"))
      (node (ref "U8") (pin "33") (pinfunction "PA24(SER3:2+)_33") (pintype "bidirectional"))
    )
    (net (code "58") (name "USB_HOST_EN") (class "Default")
      (node (ref "R31") (pin "1") (pinfunction "1_1") (pintype "passive"))
      (node (ref "U8") (pin "41") (pinfunction "PA28_41") (pintype "bidirectional"))
    )
    (net (code "59") (name "V_BATT") (class "Default")
      (node (ref "C11") (pin "1") (pinfunction "1_1") (pintype "passive"))
      (node (ref "LASER") (pin "1") (pinfunction "1_1") (pintype "passive"))
      (node (ref "R11") (pin "1") (pinfunction "1_1") (pintype "passive"))
      (node (ref "R24") (pin "1") (pinfunction "1_1") (pintype "passive"))
      (node (ref "U6") (pin "7") (pinfunction "SRN_7") (pintype "bidirectional"))
      (node (ref "U7") (pin "2") (pinfunction "BAT_2") (pintype "bidirectional"))
      (node (ref "U7") (pin "3") (pinfunction "BAT_3") (pintype "bidirectional"))
    )
    (net (code "60") (name "V_USB") (class "Default")
      (node (ref "C10") (pin "1") (pinfunction "1_1") (pintype "passive"))
      (node (ref "JP23") (pin "VBUS1") (pinfunction "VBUS_VBUS1") (pintype "bidirectional"))
      (node (ref "SUPP") (pin "1") (pinfunction "1_1") (pintype "passive"))
      (node (ref "U7") (pin "13") (pinfunction "IN_13") (pintype "bidirectional"))
    )
    (net (code "61") (name "WHT_PWM") (class "Default")
      (node (ref "R1") (pin "1") (pinfunction "1_1") (pintype "passive"))
      (node (ref "U8") (pin "23") (pinfunction "PA14(XIN/SER2:2+)_23") (pintype "bidirectional"))
    )
    (net (code "62") (name "unconnected-(JP10-PAD1-PadNC1)") (class "Default")
      (node (ref "JP10") (pin "NC1") (pinfunction "PAD1_NC1") (pintype "bidirectional"))
    )
    (net (code "63") (name "unconnected-(JP10-PAD2-PadNC2)") (class "Default")
      (node (ref "JP10") (pin "NC2") (pinfunction "PAD2_NC2") (pintype "bidirectional"))
    )
    (net (code "64") (name "unconnected-(JP22-GNDDTCT-Pad9)") (class "Default")
      (node (ref "JP22") (pin "9") (pinfunction "GNDDTCT_9") (pintype "bidirectional"))
    )
    (net (code "65") (name "unconnected-(JP22-KEY-Pad7)") (class "Default")
      (node (ref "JP22") (pin "7") (pinfunction "KEY_7") (pintype "bidirectional"))
    )
    (net (code "66") (name "unconnected-(JP22-NC{slash}TDI-Pad8)") (class "Default")
      (node (ref "JP22") (pin "8") (pinfunction "NC/TDI_8") (pintype "bidirectional"))
    )
    (net (code "67") (name "unconnected-(JP22-SWO{slash}TDO-Pad6)") (class "Default")
      (node (ref "JP22") (pin "6") (pinfunction "SWO/TDO_6") (pintype "bidirectional"))
    )
    (net (code "68") (name "unconnected-(U1-DIO1-Pad15)") (class "Default")
      (node (ref "U1") (pin "15") (pinfunction "DIO1_15") (pintype "bidirectional"))
    )
    (net (code "69") (name "unconnected-(U1-DIO2-Pad16)") (class "Default")
      (node (ref "U1") (pin "16") (pinfunction "DIO2_16") (pintype "bidirectional"))
    )
    (net (code "70") (name "unconnected-(U1-DIO3-Pad11)") (class "Default")
      (node (ref "U1") (pin "11") (pinfunction "DIO3_11") (pintype "bidirectional"))
    )
    (net (code "71") (name "unconnected-(U1-DIO4-Pad12)") (class "Default")
      (node (ref "U1") (pin "12") (pinfunction "DIO4_12") (pintype "bidirectional"))
    )
    (net (code "72") (name "unconnected-(U1-DIO5-Pad7)") (class "Default")
      (node (ref "U1") (pin "7") (pinfunction "DIO5_7") (pintype "bidirectional"))
    )
    (net (code "73") (name "unconnected-(U7-ISET-Pad16)") (class "Default")
      (node (ref "U7") (pin "16") (pinfunction "ISET_16") (pintype "bidirectional"))
    )
    (net (code "74") (name "unconnected-(U8-PA02(AIN0{slash}DAC)-Pad3)") (class "Default")
      (node (ref "U8") (pin "3") (pinfunction "PA02(AIN0/DAC)_3") (pintype "bidirectional"))
    )
    (net (code "75") (name "unconnected-(U8-PA27-Pad39)") (class "Default")
      (node (ref "U8") (pin "39") (pinfunction "PA27_39") (pintype "bidirectional"))
    )
    (net (code "76") (name "unconnected-(U8-PB10(SER4:2+)-Pad19)") (class "Default")
      (node (ref "U8") (pin "19") (pinfunction "PB10(SER4:2+)_19") (pintype "bidirectional"))
    )
    (net (code "77") (name "unconnected-(U8-PB11(SER4:3+)-Pad20)") (class "Default")
      (node (ref "U8") (pin "20") (pinfunction "PB11(SER4:3+)_20") (pintype "bidirectional"))
    )
    (net (code "78") (name "unconnected-(U8-PB22(SER5:2+)-Pad37)") (class "Default")
      (node (ref "U8") (pin "37") (pinfunction "PB22(SER5:2+)_37") (pintype "bidirectional"))
    )
    (net (code "79") (name "unconnected-(U8-PB23(SER5:3+)-Pad38)") (class "Default")
      (node (ref "U8") (pin "38") (pinfunction "PB23(SER5:3+)_38") (pintype "bidirectional"))
    )
    (net (code "80") (name "unconnected-(U9-NC-Pad4)") (class "Default")
      (node (ref "U9") (pin "4") (pinfunction "NC_4") (pintype "input"))
    )
  )
)
